# Pulser_Top.net
KiCad netlist of a schematic drawn in Altium Designer
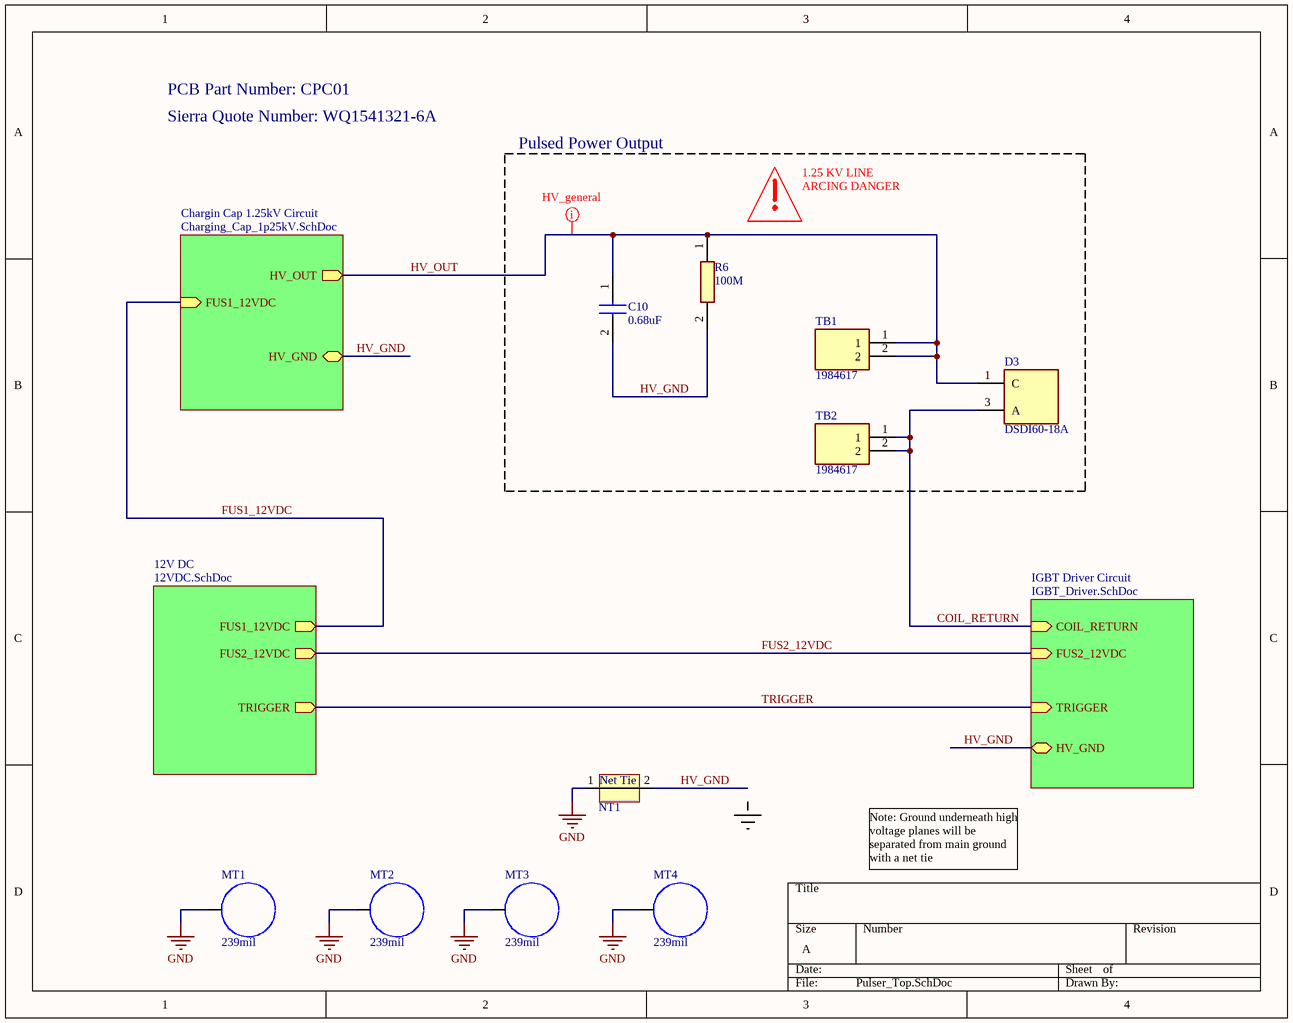
[diagram p0: Pulser_Top.SchDoc]

(export (version "E")
  (design (tool "Eeschema 10.0.6"))
  (components
    (comp (ref "C10")
      (value "0.68uF")
      (footprint "MKP1839468134HQ")
      (description "Capacitor MKP1839468134HQ")
      (fields
        (field (name "MANUFACTURER_PART_NUMBER") "MKP1839468134HQ")
        (field (name "MOUSER PART NUMBER") "75-MKP1839468134HQ")
      )
      (libsource (lib "pulser_driver_symbols") (part "MKP1839468134HQ"))
    )
    (comp (ref "D3")
      (value "DSDI60-18A")
      (footprint "TO546P530X1586X2594-2P")
      (description "Diode")
      (libsource (lib "pulser_driver_symbols") (part "DSDI60-18A"))
    )
    (comp (ref "MT1")
      (value "239mil")
      (footprint "MTHOLE_239mil")
      (fields (field (name "PART NUMBER") "MTHOLE_239") (field (name "MANUFACTURER PART NUMBER") "(NULL)"))
      (libsource (lib "pulser_driver_symbols") (part "MTHOLE_239MIL"))
    )
    (comp (ref "MT2")
      (value "239mil")
      (footprint "MTHOLE_239mil")
      (fields (field (name "PART NUMBER") "MTHOLE_239") (field (name "MANUFACTURER PART NUMBER") "(NULL)"))
      (libsource (lib "pulser_driver_symbols") (part "MTHOLE_239MIL"))
    )
    (comp (ref "MT3")
      (value "239mil")
      (footprint "MTHOLE_239mil")
      (fields (field (name "PART NUMBER") "MTHOLE_239") (field (name "MANUFACTURER PART NUMBER") "(NULL)"))
      (libsource (lib "pulser_driver_symbols") (part "MTHOLE_239MIL"))
    )
    (comp (ref "MT4")
      (value "239mil")
      (footprint "MTHOLE_239mil")
      (fields (field (name "PART NUMBER") "MTHOLE_239") (field (name "MANUFACTURER PART NUMBER") "(NULL)"))
      (libsource (lib "pulser_driver_symbols") (part "MTHOLE_239MIL"))
    )
    (comp (ref "NT1")
      (value "Net tie 50mil")
      (footprint "NET_TIE_50mil")
      (libsource (lib "pulser_driver_symbols") (part "NET_TIE_50mil"))
    )
    (comp (ref "R6")
      (value "100M")
      (footprint "HB3100MFZRE")
      (description "Resistor")
      (fields (field (name "MANUFACTURER_PART_NUMBER") "HB3100MFZRE"))
      (libsource (lib "pulser_driver_symbols") (part "HB3100MFZRE"))
    )
    (comp (ref "TB1")
      (value "1984617")
      (footprint "1984617")
      (description "Connector")
      (fields (field (name "MOUSER PART NUMBER") "651-1984617"))
      (libsource (lib "pulser_driver_symbols") (part "1984617"))
    )
    (comp (ref "TB2")
      (value "1984617")
      (footprint "1984617")
      (description "Connector")
      (fields (field (name "MOUSER PART NUMBER") "651-1984617"))
      (libsource (lib "pulser_driver_symbols") (part "1984617"))
    )
  )
  (nets
    (net (code "1") (name "/COIL_RETURN") (class "Default")
      (node (ref "D3") (pin "3") (pinfunction "A_3") (pintype "passive"))
      (node (ref "TB2") (pin "1") (pinfunction "1_1") (pintype "passive"))
      (node (ref "TB2") (pin "2") (pinfunction "2_2") (pintype "passive"))
    )
    (net (code "4") (name "/HV_GND") (class "Default")
      (node (ref "C10") (pin "2") (pinfunction "2_2") (pintype "passive"))
      (node (ref "NT1") (pin "2") (pinfunction "2_2") (pintype "passive"))
      (node (ref "R6") (pin "2") (pinfunction "2_2") (pintype "passive"))
    )
    (net (code "5") (name "/HV_OUT") (class "Default")
      (node (ref "C10") (pin "1") (pinfunction "1_1") (pintype "passive"))
      (node (ref "D3") (pin "1") (pinfunction "C_1") (pintype "passive"))
      (node (ref "R6") (pin "1") (pinfunction "1_1") (pintype "passive"))
      (node (ref "TB1") (pin "1") (pinfunction "1_1") (pintype "passive"))
      (node (ref "TB1") (pin "2") (pinfunction "2_2") (pintype "passive"))
    )
    (net (code "7") (name "GND") (class "Default")
      (node (ref "MT1") (pin "1") (pinfunction "1_1") (pintype "passive"))
      (node (ref "MT2") (pin "1") (pinfunction "1_1") (pintype "passive"))
      (node (ref "MT3") (pin "1") (pinfunction "1_1") (pintype "passive"))
      (node (ref "MT4") (pin "1") (pinfunction "1_1") (pintype "passive"))
      (node (ref "NT1") (pin "1") (pinfunction "1_1") (pintype "passive"))
    )
  )
)
